# pcb_power_ass.net
KiCad netlist of a schematic drawn in Altium Designer
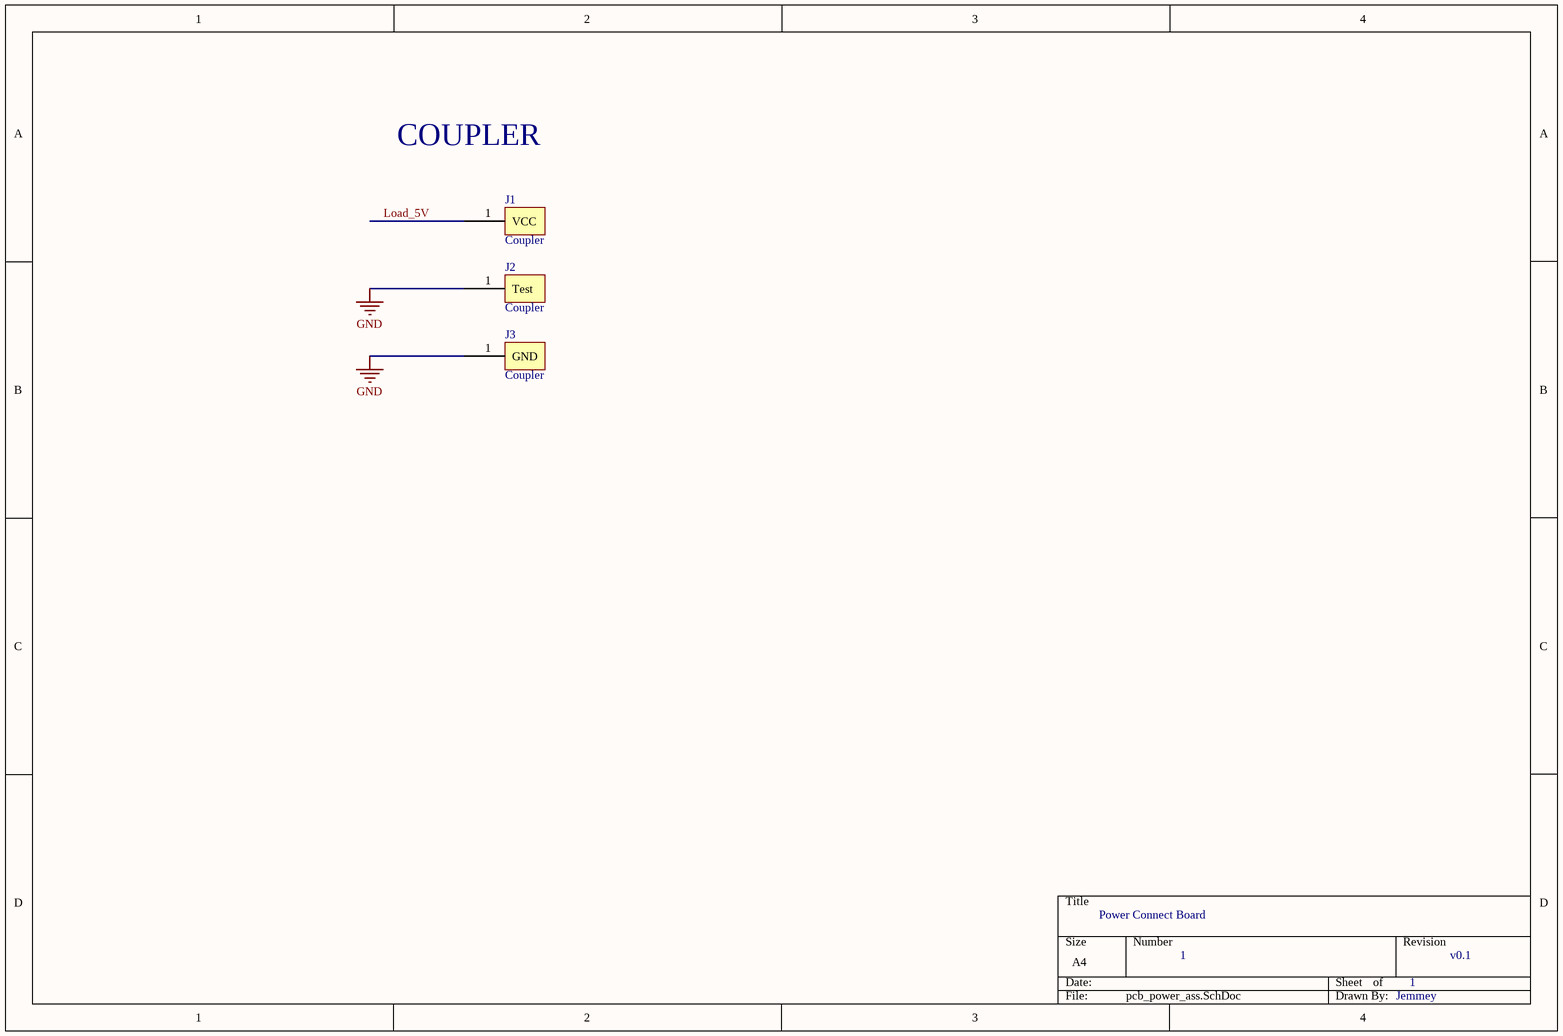
[diagram p0: pcb_power_ass.SchDoc]

(export (version "E")
  (design (tool "Eeschema 10.0.6"))
  (components
    (comp (ref "J1")
      (value "Coupler")
      (footprint "Charge_Coupler - 1")
      (description "厂家：待定；型号：待定")
      (libsource (lib "") (part "Coupler_2"))
    )
    (comp (ref "J2")
      (value "Coupler")
      (footprint "Charge_Coupler - 1")
      (description "厂家：待定；型号：待定")
      (libsource (lib "") (part "Coupler_1"))
    )
    (comp (ref "J3")
      (value "Coupler")
      (footprint "Charge_Coupler - 1")
      (description "厂家：待定；型号：待定")
      (libsource (lib "Power Connect Board") (part "Coupler"))
    )
  )
  (nets
    (net (code "1") (name "/Load_5V") (class "Default")
      (node (ref "J1") (pin "1") (pinfunction "VCC_1") (pintype "passive"))
    )
    (net (code "2") (name "GND") (class "Default")
      (node (ref "J2") (pin "1") (pinfunction "Test_1") (pintype "passive"))
      (node (ref "J3") (pin "1") (pinfunction "GND_1") (pintype "passive"))
    )
  )
)
